# Peripherals.net
KiCad netlist of a schematic drawn in Altium Designer
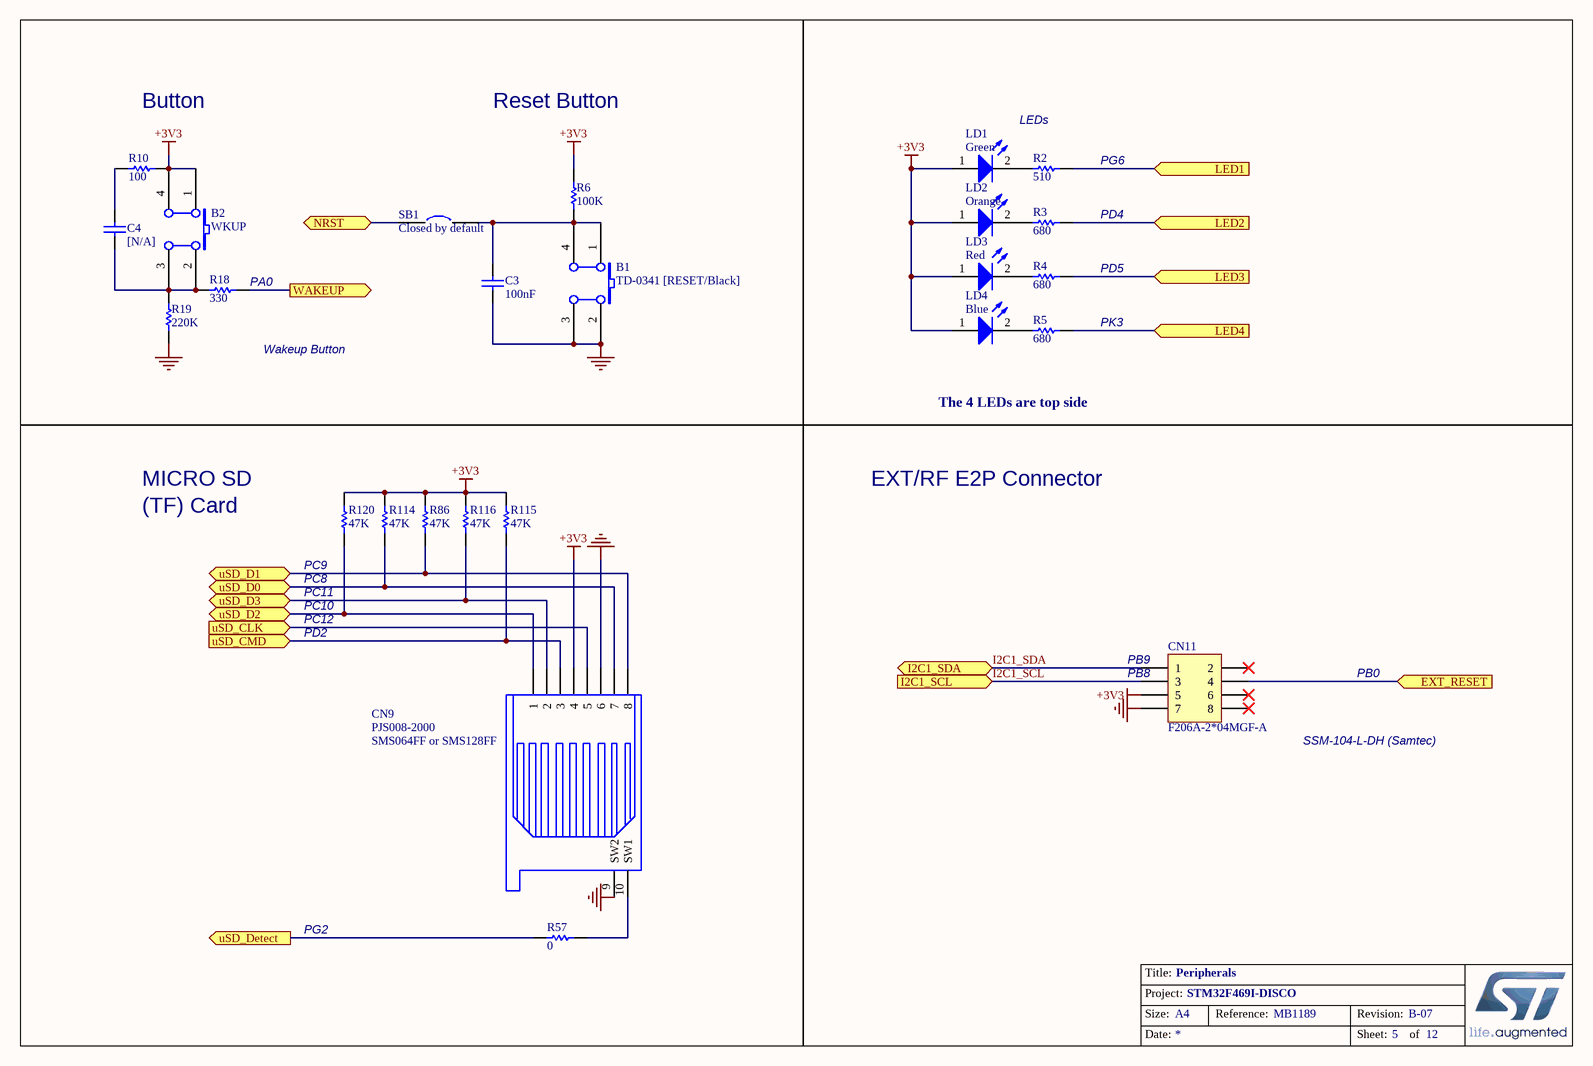
[diagram p0: Peripherals.SchDoc]

(export (version "E")
  (design (tool "Eeschema 10.0.6"))
  (components
    (comp (ref "B1")
      (value "TD-0341 [RESET/Black]")
      (footprint "PB10")
      (description "SE PUSHBUTTON")
      (libsource (lib "Documents") (part "SW PUSHBUTTON"))
    )
    (comp (ref "B2")
      (value "WKUP")
      (footprint "PB10")
      (description "SE PUSHBUTTON")
      (libsource (lib "Documents") (part "SW PUSHBUTTON"))
    )
    (comp (ref "C3")
      (value "100nF")
      (footprint "0402C")
      (description "Capacitor")
      (fields (field (name "PUBLISHER") "Altium Limited"))
      (libsource (lib "Miscellaneous Devices") (part "CAP"))
    )
    (comp (ref "C4")
      (value "[N/A]")
      (footprint "0603C")
      (description "Capacitor")
      (fields (field (name "PUBLISHER") "Altium Limited"))
      (libsource (lib "Miscellaneous Devices") (part "CAP"))
    )
    (comp (ref "CN9")
      (value "PJS008-2000")
      (footprint "MSD_PJS008_")
      (libsource (lib "MB525") (part "SMS016AFA5E"))
    )
    (comp (ref "CN11")
      (value "F206A-2*04MGF-A")
      (footprint "SSM-104-L-DH")
      (description "Header, 5-Pin, Dual row")
      (fields (field (name "PUBLISHER") "Altium Limited"))
      (libsource (lib "mb1045") (part "SSM-104-L-DH"))
    )
    (comp (ref "LD1")
      (value "Green")
      (footprint "0603D")
      (description "Typical RED, GREEN, YELLOW, AMBER GaAs LED")
      (fields (field (name "PUBLISHER") "Altium Limited"))
      (libsource (lib "Miscellaneous Devices") (part "LED2"))
    )
    (comp (ref "LD2")
      (value "Orange")
      (footprint "0603D")
      (description "Typical RED, GREEN, YELLOW, AMBER GaAs LED")
      (fields (field (name "PUBLISHER") "Altium Limited"))
      (libsource (lib "Miscellaneous Devices") (part "LED2"))
    )
    (comp (ref "LD3")
      (value "Red")
      (footprint "0603D")
      (description "Typical RED, GREEN, YELLOW, AMBER GaAs LED")
      (fields (field (name "PUBLISHER") "Altium Limited"))
      (libsource (lib "Miscellaneous Devices") (part "LED2"))
    )
    (comp (ref "LD4")
      (value "Blue")
      (footprint "0603D")
      (description "Typical RED, GREEN, YELLOW, AMBER GaAs LED")
      (fields (field (name "PUBLISHER") "Altium Limited"))
      (libsource (lib "Miscellaneous Devices") (part "LED2"))
    )
    (comp (ref "R2")
      (value "510")
      (footprint "0603R")
      (description "Resistor")
      (fields (field (name "PUBLISHER") "Altium Limited"))
      (libsource (lib "Miscellaneous Devices") (part "Res1"))
    )
    (comp (ref "R3")
      (value "680")
      (footprint "0603R")
      (description "Resistor")
      (fields (field (name "PUBLISHER") "Altium Limited"))
      (libsource (lib "Miscellaneous Devices") (part "Res1"))
    )
    (comp (ref "R4")
      (value "680")
      (footprint "0603R")
      (description "Resistor")
      (fields (field (name "PUBLISHER") "Altium Limited"))
      (libsource (lib "Miscellaneous Devices") (part "Res1"))
    )
    (comp (ref "R5")
      (value "680")
      (footprint "0603R")
      (description "Resistor")
      (fields (field (name "PUBLISHER") "Altium Limited"))
      (libsource (lib "Miscellaneous Devices") (part "Res1"))
    )
    (comp (ref "R6")
      (value "100K")
      (footprint "0603R")
      (description "Resistor")
      (fields (field (name "PUBLISHER") "Altium Limited"))
      (libsource (lib "Miscellaneous Devices") (part "res1"))
    )
    (comp (ref "R10")
      (value "100")
      (footprint "0603R")
      (description "Resistor")
      (fields (field (name "PUBLISHER") "Altium Limited"))
      (libsource (lib "Miscellaneous Devices") (part "Res1"))
    )
    (comp (ref "R18")
      (value "330")
      (footprint "0603R")
      (description "Resistor")
      (fields (field (name "PUBLISHER") "Altium Limited"))
      (libsource (lib "Miscellaneous Devices") (part "Res1"))
    )
    (comp (ref "R19")
      (value "220K")
      (footprint "0603R")
      (description "Resistor")
      (fields (field (name "PUBLISHER") "Altium Limited"))
      (libsource (lib "Miscellaneous Devices") (part "res1"))
    )
    (comp (ref "R57")
      (value "0")
      (footprint "0603R")
      (description "Resistor")
      (fields (field (name "PUBLISHER") "Altium Limited"))
      (libsource (lib "Miscellaneous Devices") (part "Res1"))
    )
    (comp (ref "R86")
      (value "47K")
      (footprint "0603R")
      (description "Resistor")
      (fields (field (name "PUBLISHER") "Altium Limited"))
      (libsource (lib "Miscellaneous Devices") (part "res1"))
    )
    (comp (ref "R114")
      (value "47K")
      (footprint "0603R")
      (description "Resistor")
      (fields (field (name "PUBLISHER") "Altium Limited"))
      (libsource (lib "Miscellaneous Devices") (part "res1"))
    )
    (comp (ref "R115")
      (value "47K")
      (footprint "0603R")
      (description "Resistor")
      (fields (field (name "PUBLISHER") "Altium Limited"))
      (libsource (lib "Miscellaneous Devices") (part "res1"))
    )
    (comp (ref "R116")
      (value "47K")
      (footprint "0603R")
      (description "Resistor")
      (fields (field (name "PUBLISHER") "Altium Limited"))
      (libsource (lib "Miscellaneous Devices") (part "res1"))
    )
    (comp (ref "R120")
      (value "47K")
      (footprint "0603R")
      (description "Resistor")
      (fields (field (name "PUBLISHER") "Altium Limited"))
      (libsource (lib "Miscellaneous Devices") (part "res1"))
    )
    (comp (ref "SB1")
      (value "Closed by default")
      (footprint "SB_0603")
      (description "Circuit Breaker")
      (fields (field (name "PUBLISHER") "Altium Limited"))
      (libsource (lib "Miscellaneous Devices") (part "Circuit Breaker"))
    )
  )
  (nets
    (net (code "1") (name "+3V3") (class "Default")
      (node (ref "B2") (pin "1") (pinfunction "A0_1") (pintype "passive"))
      (node (ref "B2") (pin "4") (pinfunction "A1_4") (pintype "passive"))
      (node (ref "CN11") (pin "5") (pinfunction "5_5") (pintype "passive"))
      (node (ref "CN9") (pin "4") (pinfunction "4_4") (pintype "passive"))
      (node (ref "LD1") (pin "1") (pinfunction "A_1") (pintype "passive"))
      (node (ref "LD2") (pin "1") (pinfunction "A_1") (pintype "passive"))
      (node (ref "LD3") (pin "1") (pinfunction "A_1") (pintype "passive"))
      (node (ref "LD4") (pin "1") (pinfunction "A_1") (pintype "passive"))
      (node (ref "R10") (pin "1") (pinfunction "1_1") (pintype "passive"))
      (node (ref "R114") (pin "1") (pinfunction "1_1") (pintype "passive"))
      (node (ref "R115") (pin "1") (pinfunction "1_1") (pintype "passive"))
      (node (ref "R116") (pin "1") (pinfunction "1_1") (pintype "passive"))
      (node (ref "R120") (pin "1") (pinfunction "1_1") (pintype "passive"))
      (node (ref "R6") (pin "1") (pinfunction "1_1") (pintype "passive"))
      (node (ref "R86") (pin "1") (pinfunction "1_1") (pintype "passive"))
    )
    (net (code "2") (name "/EXT_RESET") (class "Default")
      (node (ref "CN11") (pin "4") (pinfunction "4_4") (pintype "passive"))
    )
    (net (code "3") (name "/I2C1_SCL") (class "Default")
      (node (ref "CN11") (pin "3") (pinfunction "3_3") (pintype "passive"))
    )
    (net (code "4") (name "/I2C1_SDA") (class "Default")
      (node (ref "CN11") (pin "1") (pinfunction "1_1") (pintype "passive"))
    )
    (net (code "5") (name "/LED1") (class "Default")
      (node (ref "R2") (pin "1") (pinfunction "1_1") (pintype "passive"))
    )
    (net (code "6") (name "/LED2") (class "Default")
      (node (ref "R3") (pin "1") (pinfunction "1_1") (pintype "passive"))
    )
    (net (code "7") (name "/LED3") (class "Default")
      (node (ref "R4") (pin "1") (pinfunction "1_1") (pintype "passive"))
    )
    (net (code "8") (name "/LED4") (class "Default")
      (node (ref "R5") (pin "1") (pinfunction "1_1") (pintype "passive"))
    )
    (net (code "9") (name "/NRST") (class "Default")
      (node (ref "SB1") (pin "1") (pinfunction "1_1") (pintype "passive"))
    )
    (net (code "10") (name "/WAKEUP") (class "Default")
      (node (ref "R18") (pin "2") (pinfunction "2_2") (pintype "passive"))
    )
    (net (code "11") (name "/uSD_CLK") (class "Default")
      (node (ref "CN9") (pin "5") (pinfunction "5_5") (pintype "passive"))
    )
    (net (code "12") (name "/uSD_CMD") (class "Default")
      (node (ref "CN9") (pin "3") (pinfunction "3_3") (pintype "passive"))
      (node (ref "R115") (pin "2") (pinfunction "2_2") (pintype "passive"))
    )
    (net (code "13") (name "/uSD_D0") (class "Default")
      (node (ref "CN9") (pin "7") (pinfunction "7_7") (pintype "passive"))
      (node (ref "R114") (pin "2") (pinfunction "2_2") (pintype "passive"))
    )
    (net (code "14") (name "/uSD_D1") (class "Default")
      (node (ref "CN9") (pin "8") (pinfunction "8_8") (pintype "passive"))
      (node (ref "R86") (pin "2") (pinfunction "2_2") (pintype "passive"))
    )
    (net (code "15") (name "/uSD_D2") (class "Default")
      (node (ref "CN9") (pin "1") (pinfunction "1_1") (pintype "passive"))
      (node (ref "R120") (pin "2") (pinfunction "2_2") (pintype "passive"))
    )
    (net (code "16") (name "/uSD_D3") (class "Default")
      (node (ref "CN9") (pin "2") (pinfunction "2_2") (pintype "passive"))
      (node (ref "R116") (pin "2") (pinfunction "2_2") (pintype "passive"))
    )
    (net (code "17") (name "/uSD_Detect") (class "Default")
      (node (ref "R57") (pin "1") (pinfunction "1_1") (pintype "passive"))
    )
    (net (code "18") (name "GND") (class "Default")
      (node (ref "B1") (pin "2") (pinfunction "B0_2") (pintype "passive"))
      (node (ref "B1") (pin "3") (pinfunction "B1_3") (pintype "passive"))
      (node (ref "C3") (pin "1") (pinfunction "1_1") (pintype "passive"))
      (node (ref "CN11") (pin "7") (pinfunction "7_7") (pintype "passive"))
      (node (ref "CN9") (pin "6") (pinfunction "6_6") (pintype "passive"))
      (node (ref "CN9") (pin "9") (pinfunction "SW2_9") (pintype "passive"))
      (node (ref "R19") (pin "2") (pinfunction "2_2") (pintype "passive"))
    )
    (net (code "19") (name "Net-(B1-A0)") (class "Default")
      (node (ref "B1") (pin "1") (pinfunction "A0_1") (pintype "passive"))
      (node (ref "B1") (pin "4") (pinfunction "A1_4") (pintype "passive"))
      (node (ref "C3") (pin "2") (pinfunction "2_2") (pintype "passive"))
      (node (ref "R6") (pin "2") (pinfunction "2_2") (pintype "passive"))
      (node (ref "SB1") (pin "2") (pinfunction "2_2") (pintype "passive"))
    )
    (net (code "20") (name "Net-(B2-B0)") (class "Default")
      (node (ref "B2") (pin "2") (pinfunction "B0_2") (pintype "passive"))
      (node (ref "B2") (pin "3") (pinfunction "B1_3") (pintype "passive"))
      (node (ref "C4") (pin "2") (pinfunction "2_2") (pintype "passive"))
      (node (ref "R18") (pin "1") (pinfunction "1_1") (pintype "passive"))
      (node (ref "R19") (pin "1") (pinfunction "1_1") (pintype "passive"))
    )
    (net (code "21") (name "Net-(C4-Pad1)") (class "Default")
      (node (ref "C4") (pin "1") (pinfunction "1_1") (pintype "passive"))
      (node (ref "R10") (pin "2") (pinfunction "2_2") (pintype "passive"))
    )
    (net (code "22") (name "Net-(CN9-SW1)") (class "Default")
      (node (ref "CN9") (pin "10") (pinfunction "SW1_10") (pintype "passive"))
      (node (ref "R57") (pin "2") (pinfunction "2_2") (pintype "passive"))
    )
    (net (code "23") (name "Net-(LD1-K)") (class "Default")
      (node (ref "LD1") (pin "2") (pinfunction "K_2") (pintype "passive"))
      (node (ref "R2") (pin "2") (pinfunction "2_2") (pintype "passive"))
    )
    (net (code "24") (name "Net-(LD2-K)") (class "Default")
      (node (ref "LD2") (pin "2") (pinfunction "K_2") (pintype "passive"))
      (node (ref "R3") (pin "2") (pinfunction "2_2") (pintype "passive"))
    )
    (net (code "25") (name "Net-(LD3-K)") (class "Default")
      (node (ref "LD3") (pin "2") (pinfunction "K_2") (pintype "passive"))
      (node (ref "R4") (pin "2") (pinfunction "2_2") (pintype "passive"))
    )
    (net (code "26") (name "Net-(LD4-K)") (class "Default")
      (node (ref "LD4") (pin "2") (pinfunction "K_2") (pintype "passive"))
      (node (ref "R5") (pin "2") (pinfunction "2_2") (pintype "passive"))
    )
    (net (code "27") (name "unconnected-(CN11-Pad2)") (class "Default")
      (node (ref "CN11") (pin "2") (pinfunction "2_2") (pintype "passive+no_connect"))
    )
    (net (code "28") (name "unconnected-(CN11-Pad6)") (class "Default")
      (node (ref "CN11") (pin "6") (pinfunction "6_6") (pintype "passive+no_connect"))
    )
    (net (code "29") (name "unconnected-(CN11-Pad8)") (class "Default")
      (node (ref "CN11") (pin "8") (pinfunction "8_8") (pintype "passive+no_connect"))
    )
  )
)
